# TCAN1146_PWR_MGMT.net
KiCad netlist of a schematic drawn in Altium Designer
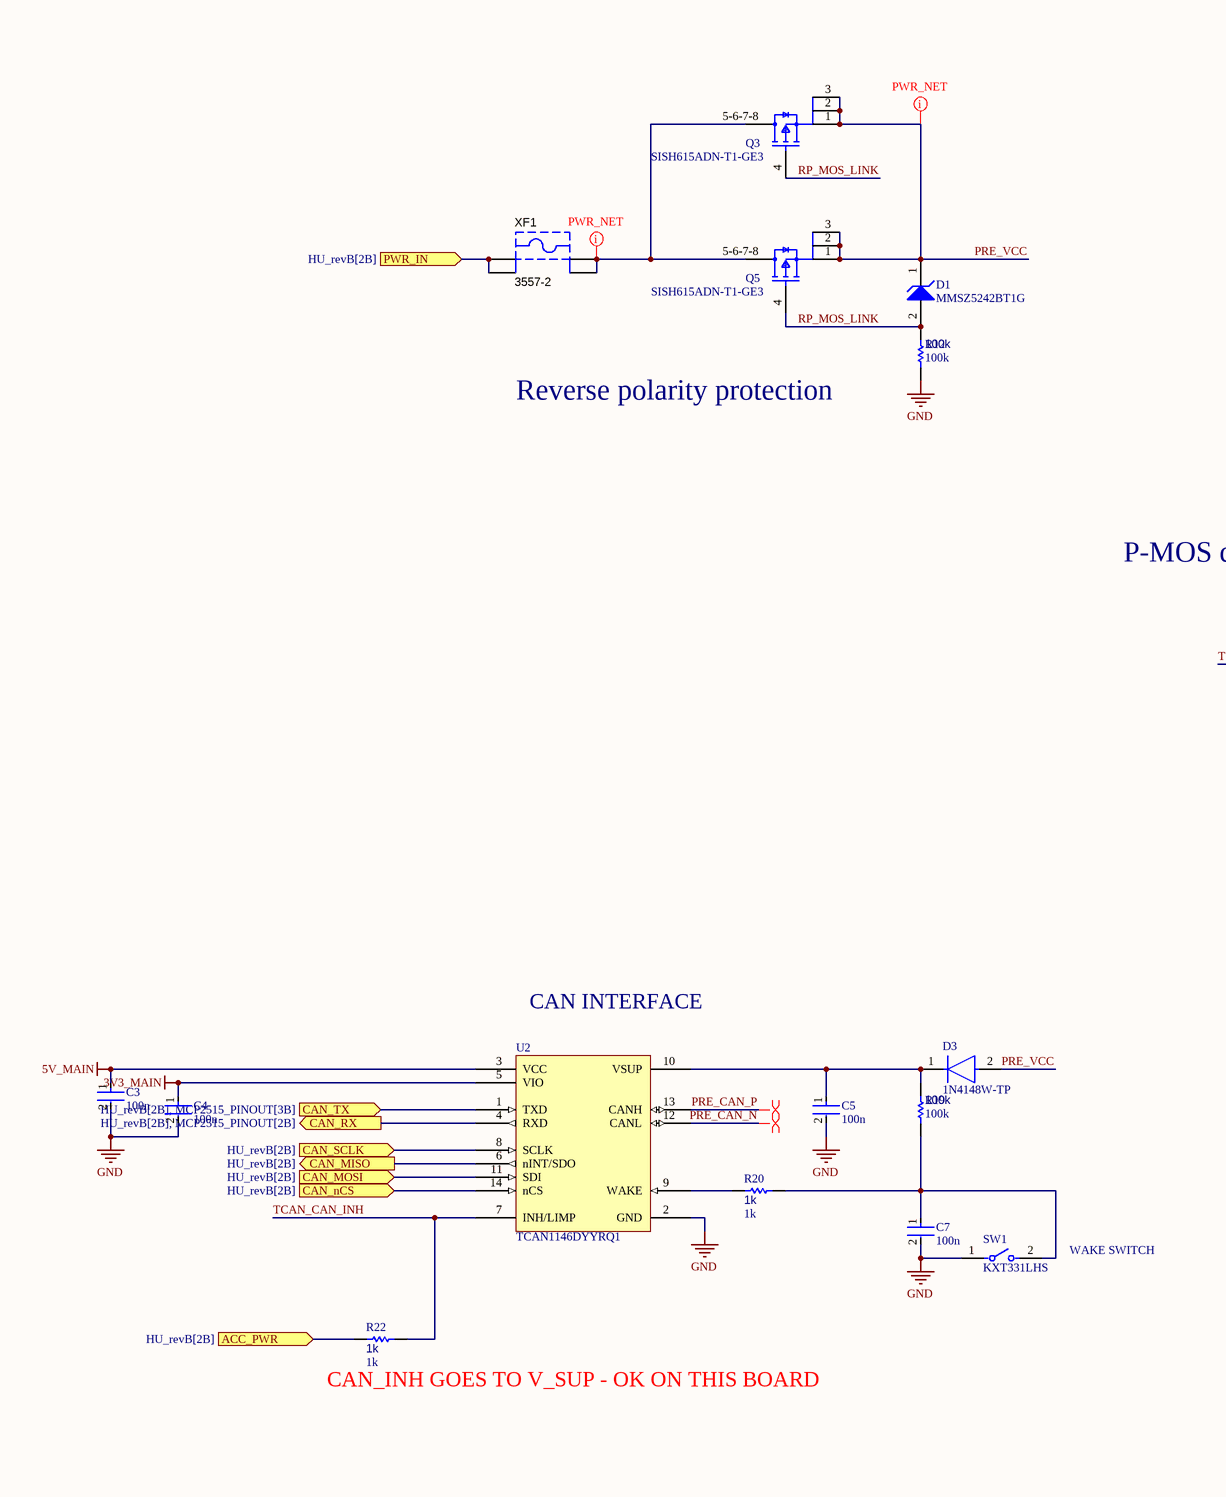
[diagram p0: TCAN1146_PWR_MGMT.SchDoc, left]
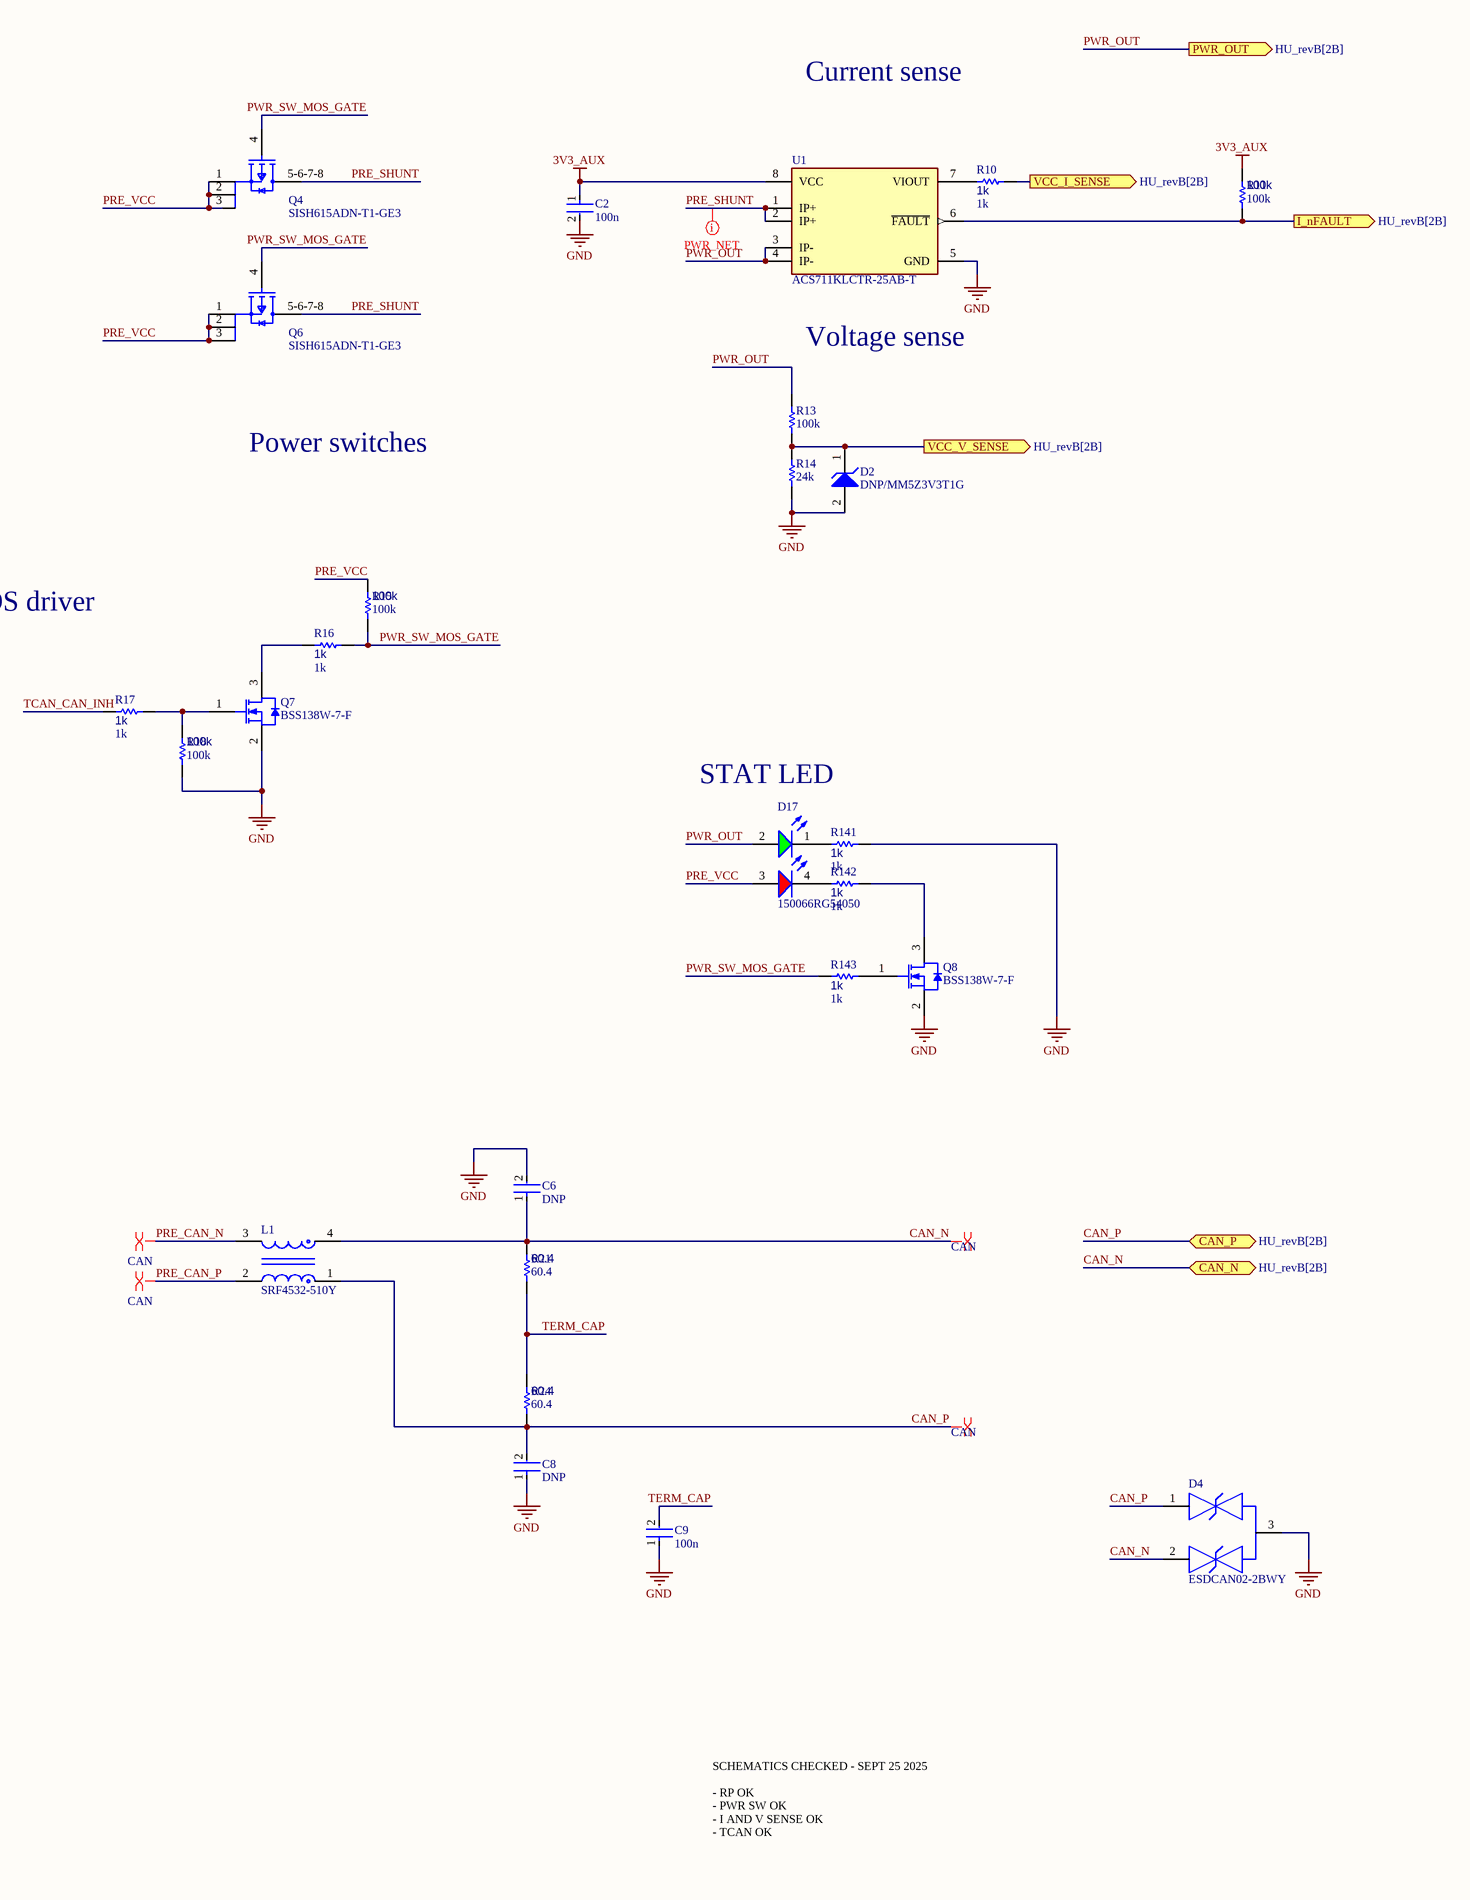
[diagram p1: TCAN1146_PWR_MGMT.SchDoc, right]

(export (version "E")
  (design (tool "Eeschema 10.0.6"))
  (components
    (comp (ref "C2")
      (value "100n")
      (footprint "FP-0402-L_1_0_0_05-W_0_5-IPC_A")
      (description "LARGE PADS, 0402 CAP, CHANGE COMMENT TO MATCH REAL P/N")
      (libsource (lib "Space Concordia") (part "b4654b650e69147ec39a6b967a45e02"))
    )
    (comp (ref "C3")
      (value "100n")
      (footprint "FP-0402-L_1_0_0_05-W_0_5-IPC_A")
      (description "LARGE PADS, 0402 CAP, CHANGE COMMENT TO MATCH REAL P/N")
      (libsource (lib "Space Concordia") (part "b4654b650e69147ec39a6b967a45e02"))
    )
    (comp (ref "C4")
      (value "100n")
      (footprint "FP-0402-L_1_0_0_05-W_0_5-IPC_A")
      (description "LARGE PADS, 0402 CAP, CHANGE COMMENT TO MATCH REAL P/N")
      (libsource (lib "Space Concordia") (part "b4654b650e69147ec39a6b967a45e02"))
    )
    (comp (ref "C5")
      (value "100n")
      (footprint "FP-0402-L_1_0_0_05-W_0_5-IPC_A")
      (description "LARGE PADS, 0402 CAP, CHANGE COMMENT TO MATCH REAL P/N")
      (libsource (lib "Space Concordia") (part "b4654b650e69147ec39a6b967a45e02"))
    )
    (comp (ref "C6")
      (value "DNP")
      (footprint "FP-0402-L_1_0_0_05-W_0_5-IPC_A")
      (description "LARGE PADS, 0402 CAP, CHANGE COMMENT TO MATCH REAL P/N")
      (libsource (lib "Space Concordia") (part "b4654b650e69147ec39a6b967a45e02"))
    )
    (comp (ref "C7")
      (value "100n")
      (footprint "FP-0402-L_1_0_0_05-W_0_5-IPC_A")
      (description "LARGE PADS, 0402 CAP, CHANGE COMMENT TO MATCH REAL P/N")
      (libsource (lib "Space Concordia") (part "b4654b650e69147ec39a6b967a45e02"))
    )
    (comp (ref "C8")
      (value "DNP")
      (footprint "FP-0402-L_1_0_0_05-W_0_5-IPC_A")
      (description "LARGE PADS, 0402 CAP, CHANGE COMMENT TO MATCH REAL P/N")
      (libsource (lib "Space Concordia") (part "b4654b650e69147ec39a6b967a45e02"))
    )
    (comp (ref "C9")
      (value "100n")
      (footprint "FP-0402-L_1_0_0_05-W_0_5-IPC_A")
      (description "LARGE PADS, 0402 CAP, CHANGE COMMENT TO MATCH REAL P/N")
      (libsource (lib "Space Concordia") (part "b4654b650e69147ec39a6b967a45e02"))
    )
    (comp (ref "D1")
      (value "MMSZ5242BT1G")
      (footprint "ONSC-SOD-123-2-425-04_V")
      (description "Zener Voltage Regulator, 500 mW, 2-Pin SOD-123, Pb-Free, Tape and Reel")
      (fields (field (name "MANUFACTURER") "On Semiconductor"))
      (libsource (lib "Altium Content Vault") (part "ONSC-K1A2-2"))
    )
    (comp (ref "D2")
      (value "DNP/MM5Z3V3T1G")
      (footprint "ONSC-SOD-523-2-502-01_V")
      (description "Zener Voltage Regulator, 500 mW, 2-Pin SOD-523, Pb-Free, Tape and Reel")
      (fields (field (name "MANUFACTURER") "On Semiconductor") (field (name "PARTNUMBER") "MM5Z3V3T1G"))
      (libsource (lib "Altium Content Vault") (part "ONSC-K1A2-2"))
    )
    (comp (ref "D3")
      (value "1N4148W-TP")
      (footprint "FP-SOD-123-IPC_A")
      (description "DIODE GEN PURP 100V 150MA SOD123")
      (libsource (lib "Altium Content Vault") (part "d7152d700b627762746794eb795d46e"))
    )
    (comp (ref "D4")
      (value "ESDCAN02-2BWY")
      (footprint "FP-SOT323-3L-MFG")
      (description "TVS DIODE 26.5V 44V SOT323-3")
      (fields
        (field (name "MANUFACTURER") "STMicroelectronics")
        (field (name "OCTOPART") "https://octopart.com/esdcan02-2bwy-stmicroelectronics-58631133")
      )
      (libsource (lib "Altium Content Vault") (part "0b9019fb5e52ed66df21ec1535be59d"))
    )
    (comp (ref "D17")
      (value "150066RG54050")
      (footprint "WL-SBCD_0606")
      (description "Led, Red/Grn, 180Mcd/230Mcd, 624Nm/525Nm Rohs Compliant: Yes")
      (fields (field (name "SOURCE") "rgled.SchLib"))
      (libsource (lib "Space Concordia") (part "CMP-004-00034-2"))
    )
    (comp (ref "L1")
      (value "SRF4532-510Y")
      (footprint "FP-SRF4532-MFG")
      (description "CMC 51UH 200MA 2LN 2KOHM SMD")
      (fields (field (name "TOLERANCE") "50%"))
      (libsource (lib "Altium Content Vault") (part "aca3f6a10b859f211cca95010157f3b"))
    )
    (comp (ref "Q3")
      (value "SISH615ADN-T1-GE3")
      (footprint "SISH615ADN-T1-GE3-Footprint-1")
      (description "Trans MOSFET P-CH 20V 22.1A 8-Pin PowerPAK 1212 EP T/R")
      (libsource (lib "Space Concordia") (part "CMP-013-00036-4"))
    )
    (comp (ref "Q4")
      (value "SISH615ADN-T1-GE3")
      (footprint "SISH615ADN-T1-GE3-Footprint-1")
      (description "Trans MOSFET P-CH 20V 22.1A 8-Pin PowerPAK 1212 EP T/R")
      (libsource (lib "Space Concordia") (part "CMP-013-00036-4"))
    )
    (comp (ref "Q5")
      (value "SISH615ADN-T1-GE3")
      (footprint "SISH615ADN-T1-GE3-Footprint-1")
      (description "Trans MOSFET P-CH 20V 22.1A 8-Pin PowerPAK 1212 EP T/R")
      (libsource (lib "Space Concordia") (part "CMP-013-00036-4"))
    )
    (comp (ref "Q6")
      (value "SISH615ADN-T1-GE3")
      (footprint "SISH615ADN-T1-GE3-Footprint-1")
      (description "Trans MOSFET P-CH 20V 22.1A 8-Pin PowerPAK 1212 EP T/R")
      (libsource (lib "Space Concordia") (part "CMP-013-00036-4"))
    )
    (comp (ref "Q7")
      (value "BSS138W-7-F")
      (footprint "DIOD-SOT323-3_V")
      (fields (field (name "MANUFACTURER") "DiodesIncorporated"))
      (libsource (lib "Altium Content Vault") (part "NEMOS-GSD-3"))
    )
    (comp (ref "Q8")
      (value "BSS138W-7-F")
      (footprint "DIOD-SOT323-3_V")
      (fields (field (name "MANUFACTURER") "DiodesIncorporated"))
      (libsource (lib "Altium Content Vault") (part "NEMOS-GSD-3"))
    )
    (comp (ref "R10")
      (value "1k")
      (footprint "R0603B")
      (description "Resistor")
      (fields (field (name "ALTIUM_VALUE") "1k"))
      (libsource (lib "Space Concordia") (part "Resistor"))
    )
    (comp (ref "R11")
      (value "100k")
      (footprint "R0603B")
      (description "Resistor")
      (fields (field (name "ALTIUM_VALUE") "100k"))
      (libsource (lib "Space Concordia") (part "Resistor"))
    )
    (comp (ref "R12")
      (value "100k")
      (footprint "R0603B")
      (description "Resistor")
      (fields (field (name "ALTIUM_VALUE") "100k"))
      (libsource (lib "Space Concordia") (part "Resistor"))
    )
    (comp (ref "R13")
      (value "100k")
      (footprint "R0603B")
      (description "Resistor")
      (libsource (lib "Space Concordia") (part "Resistor"))
    )
    (comp (ref "R14")
      (value "24k")
      (footprint "R0603B")
      (description "Resistor")
      (libsource (lib "Space Concordia") (part "Resistor"))
    )
    (comp (ref "R15")
      (value "100k")
      (footprint "R0603B")
      (description "Resistor")
      (fields (field (name "ALTIUM_VALUE") "100k"))
      (libsource (lib "Space Concordia") (part "Resistor"))
    )
    (comp (ref "R16")
      (value "1k")
      (footprint "R0603B")
      (description "Resistor")
      (fields (field (name "ALTIUM_VALUE") "1k"))
      (libsource (lib "Space Concordia") (part "Resistor"))
    )
    (comp (ref "R17")
      (value "1k")
      (footprint "R0603B")
      (description "Resistor")
      (fields (field (name "ALTIUM_VALUE") "1k"))
      (libsource (lib "Space Concordia") (part "Resistor"))
    )
    (comp (ref "R18")
      (value "100k")
      (footprint "R0603B")
      (description "Resistor")
      (fields (field (name "ALTIUM_VALUE") "100k"))
      (libsource (lib "Space Concordia") (part "Resistor"))
    )
    (comp (ref "R19")
      (value "100k")
      (footprint "R0603B")
      (description "Resistor")
      (fields (field (name "ALTIUM_VALUE") "100k"))
      (libsource (lib "Space Concordia") (part "Resistor"))
    )
    (comp (ref "R20")
      (value "1k")
      (footprint "R0603B")
      (description "Resistor")
      (fields (field (name "ALTIUM_VALUE") "1k"))
      (libsource (lib "Space Concordia") (part "Resistor"))
    )
    (comp (ref "R21")
      (value "60.4")
      (footprint "R0603B")
      (description "Resistor")
      (fields (field (name "ALTIUM_VALUE") "60.4"))
      (libsource (lib "Space Concordia") (part "Resistor"))
    )
    (comp (ref "R22")
      (value "1k")
      (footprint "R0603B")
      (description "Resistor")
      (fields (field (name "ALTIUM_VALUE") "1k"))
      (libsource (lib "Space Concordia") (part "Resistor"))
    )
    (comp (ref "R24")
      (value "60.4")
      (footprint "R0603B")
      (description "Resistor")
      (fields (field (name "ALTIUM_VALUE") "60.4"))
      (libsource (lib "Space Concordia") (part "Resistor"))
    )
    (comp (ref "R141")
      (value "1k")
      (footprint "R0603B")
      (description "Resistor")
      (fields (field (name "ALTIUM_VALUE") "1k"))
      (libsource (lib "Space Concordia") (part "Resistor"))
    )
    (comp (ref "R142")
      (value "1k")
      (footprint "R0603B")
      (description "Resistor")
      (fields (field (name "ALTIUM_VALUE") "1k"))
      (libsource (lib "Space Concordia") (part "Resistor"))
    )
    (comp (ref "R143")
      (value "1k")
      (footprint "R0603B")
      (description "Resistor")
      (fields (field (name "ALTIUM_VALUE") "1k"))
      (libsource (lib "Space Concordia") (part "Resistor"))
    )
    (comp (ref "SW1")
      (value "KXT331LHS")
      (footprint "FP-KXT331LHS-MFG")
      (description "SWITCH TACTILE SPST-NO 0.02A 15V")
      (libsource (lib "Altium Content Vault") (part "bb27bde45df87f1f469753f287ef5ae"))
    )
    (comp (ref "U1")
      (value "ACS711KLCTR-25AB-T")
      (footprint "FP-LC-8-IPC_A")
      (description "SENSOR CURRENT HALL 25A AC/DC")
      (libsource (lib "Altium Content Vault") (part "eeba3158841281b4ae542a6e24976ab"))
    )
    (comp (ref "U2")
      (value "TCAN1146DYYRQ1")
      (footprint "TCAN1146DYYRQ1-Footprint-1")
      (libsource (lib "Space Concordia") (part "CMP-015-00012-2"))
    )
    (comp (ref "XF1")
      (value "3557-2")
      (footprint "KSTN-3557-2")
      (description "FUSE HOLDER, PCB MOUNT, 500VAC, 20A, ROHS")
      (fields (field (name "VOLTAGE") "500V") (field (name "MANUFACTURER") "Keystone-Electronics"))
      (libsource (lib "Altium Content Vault") (part "FUSE_HOLDER-4"))
    )
  )
  (nets
    (net (code "1") (name "/ACC_PWR") (class "Default")
      (node (ref "R22") (pin "1") (pinfunction "1_1") (pintype "passive"))
    )
    (net (code "2") (name "/CAN_MISO") (class "Default")
      (node (ref "U2") (pin "6") (pinfunction "nINT/SDO_6") (pintype "output"))
    )
    (net (code "3") (name "/CAN_MOSI") (class "Default")
      (node (ref "U2") (pin "11") (pinfunction "SDI_11") (pintype "input"))
    )
    (net (code "4") (name "/CAN_N") (class "Default")
      (node (ref "C6") (pin "1") (pinfunction "1_1") (pintype "passive"))
      (node (ref "D4") (pin "2") (pinfunction "2_2") (pintype "passive"))
      (node (ref "L1") (pin "4") (pinfunction "4_4") (pintype "passive"))
      (node (ref "R21") (pin "2") (pinfunction "2_2") (pintype "passive"))
    )
    (net (code "5") (name "/CAN_P") (class "Default")
      (node (ref "C8") (pin "2") (pinfunction "2_2") (pintype "passive"))
      (node (ref "D4") (pin "1") (pinfunction "1_1") (pintype "passive"))
      (node (ref "L1") (pin "1") (pinfunction "1_1") (pintype "passive"))
      (node (ref "R24") (pin "1") (pinfunction "1_1") (pintype "passive"))
    )
    (net (code "6") (name "/CAN_RX") (class "Default")
      (node (ref "U2") (pin "4") (pinfunction "RXD_4") (pintype "output"))
    )
    (net (code "7") (name "/CAN_SCLK") (class "Default")
      (node (ref "U2") (pin "8") (pinfunction "SCLK_8") (pintype "input"))
    )
    (net (code "8") (name "/CAN_TX") (class "Default")
      (node (ref "U2") (pin "1") (pinfunction "TXD_1") (pintype "input"))
    )
    (net (code "9") (name "/CAN_nCS") (class "Default")
      (node (ref "U2") (pin "14") (pinfunction "nCS_14") (pintype "input"))
    )
    (net (code "10") (name "/I_nFAULT") (class "Default")
      (node (ref "R11") (pin "1") (pinfunction "1_1") (pintype "passive"))
      (node (ref "U1") (pin "6") (pinfunction "~{FAULT}_6") (pintype "output"))
    )
    (net (code "11") (name "/PRE_CAN_N") (class "Default")
      (node (ref "L1") (pin "3") (pinfunction "3_3") (pintype "passive"))
      (node (ref "U2") (pin "12") (pinfunction "CANL_12") (pintype "bidirectional"))
    )
    (net (code "12") (name "/PRE_CAN_P") (class "Default")
      (node (ref "L1") (pin "2") (pinfunction "2_2") (pintype "passive"))
      (node (ref "U2") (pin "13") (pinfunction "CANH_13") (pintype "bidirectional"))
    )
    (net (code "13") (name "/PRE_SHUNT") (class "Default")
      (node (ref "Q4") (pin "5-6-7-8") (pinfunction "D_5-6-7-8") (pintype "passive"))
      (node (ref "Q6") (pin "5-6-7-8") (pinfunction "D_5-6-7-8") (pintype "passive"))
      (node (ref "U1") (pin "1") (pinfunction "IP+_1") (pintype "passive"))
      (node (ref "U1") (pin "2") (pinfunction "IP+_2") (pintype "passive"))
    )
    (net (code "14") (name "/PRE_VCC") (class "Default")
      (node (ref "D1") (pin "1") (pinfunction "K_1") (pintype "passive"))
      (node (ref "D17") (pin "3") (pinfunction "A_3") (pintype "passive"))
      (node (ref "D3") (pin "2") (pinfunction "A_2") (pintype "passive"))
      (node (ref "Q3") (pin "1") (pinfunction "S_1") (pintype "passive"))
      (node (ref "Q3") (pin "2") (pinfunction "S_2") (pintype "passive"))
      (node (ref "Q3") (pin "3") (pinfunction "S_3") (pintype "passive"))
      (node (ref "Q4") (pin "1") (pinfunction "S_1") (pintype "passive"))
      (node (ref "Q4") (pin "2") (pinfunction "S_2") (pintype "passive"))
      (node (ref "Q4") (pin "3") (pinfunction "S_3") (pintype "passive"))
      (node (ref "Q5") (pin "1") (pinfunction "S_1") (pintype "passive"))
      (node (ref "Q5") (pin "2") (pinfunction "S_2") (pintype "passive"))
      (node (ref "Q5") (pin "3") (pinfunction "S_3") (pintype "passive"))
      (node (ref "Q6") (pin "1") (pinfunction "S_1") (pintype "passive"))
      (node (ref "Q6") (pin "2") (pinfunction "S_2") (pintype "passive"))
      (node (ref "Q6") (pin "3") (pinfunction "S_3") (pintype "passive"))
      (node (ref "R15") (pin "2") (pinfunction "2_2") (pintype "passive"))
    )
    (net (code "15") (name "/PWR_IN") (class "Default")
      (node (ref "XF1") (pin "1") (pinfunction "1_1") (pintype "passive"))
      (node (ref "XF1") (pin "2") (pinfunction "2_2") (pintype "passive"))
    )
    (net (code "16") (name "/PWR_OUT") (class "Default")
      (node (ref "D17") (pin "2") (pinfunction "A_2") (pintype "passive"))
      (node (ref "R13") (pin "2") (pinfunction "2_2") (pintype "passive"))
      (node (ref "U1") (pin "3") (pinfunction "IP-_3") (pintype "passive"))
      (node (ref "U1") (pin "4") (pinfunction "IP-_4") (pintype "passive"))
    )
    (net (code "17") (name "/PWR_SW_MOS_GATE") (class "Default")
      (node (ref "Q4") (pin "4") (pinfunction "G_4") (pintype "passive"))
      (node (ref "Q6") (pin "4") (pinfunction "G_4") (pintype "passive"))
      (node (ref "R143") (pin "1") (pinfunction "1_1") (pintype "passive"))
      (node (ref "R15") (pin "1") (pinfunction "1_1") (pintype "passive"))
      (node (ref "R16") (pin "2") (pinfunction "2_2") (pintype "passive"))
    )
    (net (code "18") (name "/RP_MOS_LINK") (class "Default")
      (node (ref "D1") (pin "2") (pinfunction "A_2") (pintype "passive"))
      (node (ref "Q3") (pin "4") (pinfunction "G_4") (pintype "passive"))
      (node (ref "Q5") (pin "4") (pinfunction "G_4") (pintype "passive"))
      (node (ref "R12") (pin "2") (pinfunction "2_2") (pintype "passive"))
    )
    (net (code "19") (name "/TCAN_CAN_INH") (class "Default")
      (node (ref "R17") (pin "1") (pinfunction "1_1") (pintype "passive"))
      (node (ref "R22") (pin "2") (pinfunction "2_2") (pintype "passive"))
      (node (ref "U2") (pin "7") (pinfunction "INH/LIMP_7") (pintype "passive"))
    )
    (net (code "20") (name "/TERM_CAP") (class "Default")
      (node (ref "C9") (pin "2") (pinfunction "2_2") (pintype "passive"))
      (node (ref "R21") (pin "1") (pinfunction "1_1") (pintype "passive"))
      (node (ref "R24") (pin "2") (pinfunction "2_2") (pintype "passive"))
    )
    (net (code "21") (name "/VCC_I_SENSE") (class "Default")
      (node (ref "R10") (pin "1") (pinfunction "1_1") (pintype "passive"))
    )
    (net (code "22") (name "/VCC_V_SENSE") (class "Default")
      (node (ref "D2") (pin "1") (pinfunction "K_1") (pintype "passive"))
      (node (ref "R13") (pin "1") (pinfunction "1_1") (pintype "passive"))
      (node (ref "R14") (pin "2") (pinfunction "2_2") (pintype "passive"))
    )
    (net (code "23") (name "3V3_AUX") (class "Default")
      (node (ref "C2") (pin "1") (pinfunction "1_1") (pintype "passive"))
      (node (ref "R11") (pin "2") (pinfunction "2_2") (pintype "passive"))
      (node (ref "U1") (pin "8") (pinfunction "VCC_8") (pintype "power_in"))
    )
    (net (code "24") (name "3V3_MAIN") (class "Default")
      (node (ref "C4") (pin "1") (pinfunction "1_1") (pintype "passive"))
      (node (ref "U2") (pin "5") (pinfunction "VIO_5") (pintype "power_in"))
    )
    (net (code "25") (name "5V_MAIN") (class "Default")
      (node (ref "C3") (pin "1") (pinfunction "1_1") (pintype "passive"))
      (node (ref "U2") (pin "3") (pinfunction "VCC_3") (pintype "power_in"))
    )
    (net (code "26") (name "GND") (class "Default")
      (node (ref "C2") (pin "2") (pinfunction "2_2") (pintype "passive"))
      (node (ref "C3") (pin "2") (pinfunction "2_2") (pintype "passive"))
      (node (ref "C4") (pin "2") (pinfunction "2_2") (pintype "passive"))
      (node (ref "C5") (pin "2") (pinfunction "2_2") (pintype "passive"))
      (node (ref "C6") (pin "2") (pinfunction "2_2") (pintype "passive"))
      (node (ref "C7") (pin "2") (pinfunction "2_2") (pintype "passive"))
      (node (ref "C8") (pin "1") (pinfunction "1_1") (pintype "passive"))
      (node (ref "C9") (pin "1") (pinfunction "1_1") (pintype "passive"))
      (node (ref "D2") (pin "2") (pinfunction "A_2") (pintype "passive"))
      (node (ref "D4") (pin "3") (pinfunction "3_3") (pintype "passive"))
      (node (ref "Q7") (pin "2") (pinfunction "S_2") (pintype "passive"))
      (node (ref "Q8") (pin "2") (pinfunction "S_2") (pintype "passive"))
      (node (ref "R12") (pin "1") (pinfunction "1_1") (pintype "passive"))
      (node (ref "R14") (pin "1") (pinfunction "1_1") (pintype "passive"))
      (node (ref "R141") (pin "2") (pinfunction "2_2") (pintype "passive"))
      (node (ref "R18") (pin "1") (pinfunction "1_1") (pintype "passive"))
      (node (ref "SW1") (pin "1") (pinfunction "1_1") (pintype "passive"))
      (node (ref "U1") (pin "5") (pinfunction "GND_5") (pintype "power_in"))
      (node (ref "U2") (pin "2") (pinfunction "GND_2") (pintype "power_in"))
    )
    (net (code "27") (name "Net-(C7-Pad1)") (class "Default")
      (node (ref "C7") (pin "1") (pinfunction "1_1") (pintype "passive"))
      (node (ref "R19") (pin "1") (pinfunction "1_1") (pintype "passive"))
      (node (ref "R20") (pin "2") (pinfunction "2_2") (pintype "passive"))
      (node (ref "SW1") (pin "2") (pinfunction "2_2") (pintype "passive"))
    )
    (net (code "28") (name "Net-(D3-C)") (class "Default")
      (node (ref "C5") (pin "1") (pinfunction "1_1") (pintype "passive"))
      (node (ref "D3") (pin "1") (pinfunction "C_1") (pintype "passive"))
      (node (ref "R19") (pin "2") (pinfunction "2_2") (pintype "passive"))
      (node (ref "U2") (pin "10") (pinfunction "VSUP_10") (pintype "power_in"))
    )
    (net (code "29") (name "Net-(D17-K-Pad1)") (class "Default")
      (node (ref "D17") (pin "1") (pinfunction "K_1") (pintype "passive"))
      (node (ref "R141") (pin "1") (pinfunction "1_1") (pintype "passive"))
    )
    (net (code "30") (name "Net-(D17-K-Pad4)") (class "Default")
      (node (ref "D17") (pin "4") (pinfunction "K_4") (pintype "passive"))
      (node (ref "R142") (pin "1") (pinfunction "1_1") (pintype "passive"))
    )
    (net (code "31") (name "Net-(Q3-D)") (class "Default")
      (node (ref "Q3") (pin "5-6-7-8") (pinfunction "D_5-6-7-8") (pintype "passive"))
      (node (ref "Q5") (pin "5-6-7-8") (pinfunction "D_5-6-7-8") (pintype "passive"))
      (node (ref "XF1") (pin "3") (pinfunction "3_3") (pintype "passive"))
      (node (ref "XF1") (pin "4") (pinfunction "4_4") (pintype "passive"))
    )
    (net (code "32") (name "Net-(Q7-D)") (class "Default")
      (node (ref "Q7") (pin "3") (pinfunction "D_3") (pintype "passive"))
      (node (ref "R16") (pin "1") (pinfunction "1_1") (pintype "passive"))
    )
    (net (code "33") (name "Net-(Q7-G)") (class "Default")
      (node (ref "Q7") (pin "1") (pinfunction "G_1") (pintype "passive"))
      (node (ref "R17") (pin "2") (pinfunction "2_2") (pintype "passive"))
      (node (ref "R18") (pin "2") (pinfunction "2_2") (pintype "passive"))
    )
    (net (code "34") (name "Net-(Q8-D)") (class "Default")
      (node (ref "Q8") (pin "3") (pinfunction "D_3") (pintype "passive"))
      (node (ref "R142") (pin "2") (pinfunction "2_2") (pintype "passive"))
    )
    (net (code "35") (name "Net-(Q8-G)") (class "Default")
      (node (ref "Q8") (pin "1") (pinfunction "G_1") (pintype "passive"))
      (node (ref "R143") (pin "2") (pinfunction "2_2") (pintype "passive"))
    )
    (net (code "36") (name "Net-(U1-VIOUT)") (class "Default")
      (node (ref "R10") (pin "2") (pinfunction "2_2") (pintype "passive"))
      (node (ref "U1") (pin "7") (pinfunction "VIOUT_7") (pintype "passive"))
    )
    (net (code "37") (name "Net-(U2-WAKE)") (class "Default")
      (node (ref "R20") (pin "1") (pinfunction "1_1") (pintype "passive"))
      (node (ref "U2") (pin "9") (pinfunction "WAKE_9") (pintype "input"))
    )
  )
)
